# IMU.net
KiCad netlist of a schematic drawn in Altium Designer
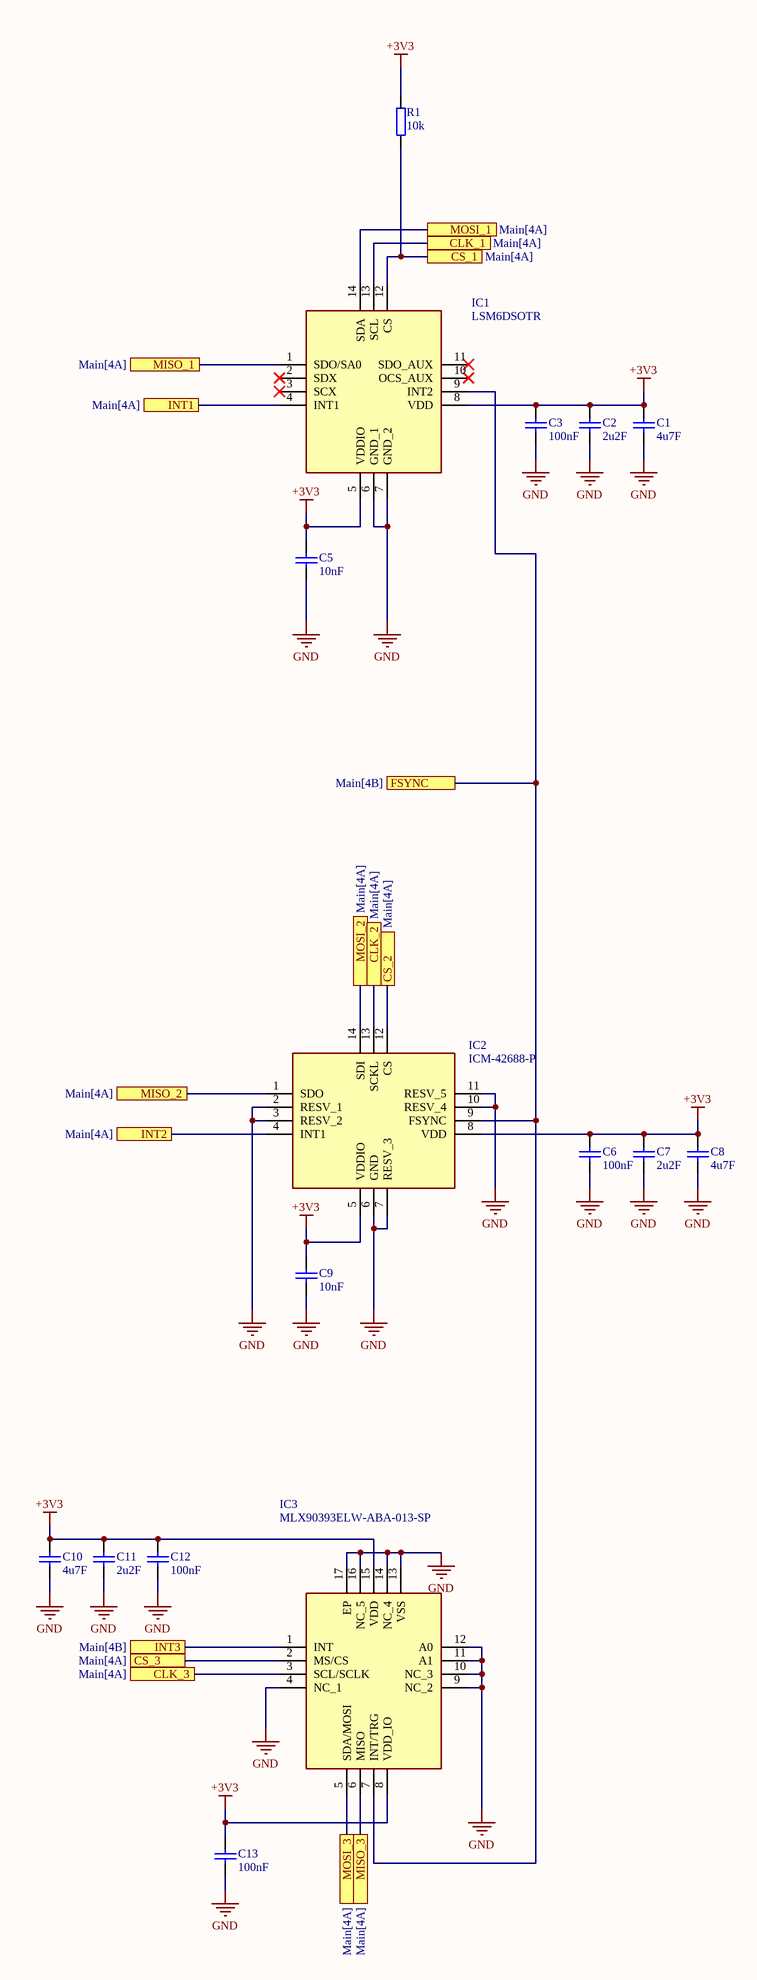
[diagram p0: IMU.SchDoc]

(export (version "E")
  (design (tool "Eeschema 10.0.6"))
  (components
    (comp (ref "C1")
      (value "4u7F")
      (footprint "CAP0805")
      (fields
        (field (name "VOLTAGE") "35V")
        (field (name "MANUFACTURER_PART_NUMBER") "GRM21BR61H475ME51L")
        (field (name "Comment") "Cap0805")
      )
      (libsource (lib "capacitorsSMD") (part "Cap0805"))
    )
    (comp (ref "C2")
      (value "2u2F")
      (footprint "CAP0603")
      (fields
        (field (name "VOLTAGE") "50V")
        (field (name "MANUFACTURER_PART_NUMBER") "GRT188R61H225KE13D")
        (field (name "Comment") "Cap0603")
      )
      (libsource (lib "capacitorsSMD") (part "Cap0603"))
    )
    (comp (ref "C3")
      (value "100nF")
      (footprint "CAP0402")
      (fields
        (field (name "VOLTAGE") "50V")
        (field (name "MANUFACTURER_PART_NUMBER") "GRM155R71H104ME14D")
        (field (name "Comment") "Cap0402")
      )
      (libsource (lib "capacitorsSMD") (part "Cap0402"))
    )
    (comp (ref "C5")
      (value "10nF")
      (footprint "CAP0402")
      (fields
        (field (name "VOLTAGE") "50V")
        (field (name "MANUFACTURER_PART_NUMBER") "GRM155R71H103MA88D")
        (field (name "Comment") "Cap0402")
      )
      (libsource (lib "capacitorsSMD") (part "Cap0402"))
    )
    (comp (ref "C6")
      (value "100nF")
      (footprint "CAP0402")
      (fields
        (field (name "VOLTAGE") "50V")
        (field (name "MANUFACTURER_PART_NUMBER") "GRM155R71H104ME14D")
        (field (name "Comment") "Cap0402")
      )
      (libsource (lib "capacitorsSMD") (part "Cap0402"))
    )
    (comp (ref "C7")
      (value "2u2F")
      (footprint "CAP0603")
      (fields
        (field (name "VOLTAGE") "50V")
        (field (name "MANUFACTURER_PART_NUMBER") "GRT188R61H225KE13D")
        (field (name "Comment") "Cap0603")
      )
      (libsource (lib "capacitorsSMD") (part "Cap0603"))
    )
    (comp (ref "C8")
      (value "4u7F")
      (footprint "CAP0805")
      (fields
        (field (name "VOLTAGE") "35V")
        (field (name "MANUFACTURER_PART_NUMBER") "GRM21BR61H475ME51L")
        (field (name "Comment") "Cap0805")
      )
      (libsource (lib "capacitorsSMD") (part "Cap0805"))
    )
    (comp (ref "C9")
      (value "10nF")
      (footprint "CAP0402")
      (fields
        (field (name "VOLTAGE") "50V")
        (field (name "MANUFACTURER_PART_NUMBER") "GRM155R71H103MA88D")
        (field (name "Comment") "Cap0402")
      )
      (libsource (lib "capacitorsSMD") (part "Cap0402"))
    )
    (comp (ref "C10")
      (value "4u7F")
      (footprint "CAP0805")
      (fields
        (field (name "VOLTAGE") "35V")
        (field (name "MANUFACTURER_PART_NUMBER") "GRM21BR61H475ME51L")
        (field (name "Comment") "Cap0805")
      )
      (libsource (lib "capacitorsSMD") (part "Cap0805"))
    )
    (comp (ref "C11")
      (value "2u2F")
      (footprint "CAP0603")
      (fields
        (field (name "VOLTAGE") "50V")
        (field (name "MANUFACTURER_PART_NUMBER") "GRT188R61H225KE13D")
        (field (name "Comment") "Cap0603")
      )
      (libsource (lib "capacitorsSMD") (part "Cap0603"))
    )
    (comp (ref "C12")
      (value "100nF")
      (footprint "CAP0402")
      (fields
        (field (name "VOLTAGE") "50V")
        (field (name "MANUFACTURER_PART_NUMBER") "GRM155R71H104ME14D")
        (field (name "Comment") "Cap0402")
      )
      (libsource (lib "capacitorsSMD") (part "Cap0402"))
    )
    (comp (ref "C13")
      (value "100nF")
      (footprint "CAP0402")
      (fields
        (field (name "VOLTAGE") "50V")
        (field (name "MANUFACTURER_PART_NUMBER") "GRM155R71H104ME14D")
        (field (name "Comment") "Cap0402")
      )
      (libsource (lib "capacitorsSMD") (part "Cap0402"))
    )
    (comp (ref "IC1")
      (value "LSM6DSOTR")
      (footprint "SamacSys:LSM6DS3USTR")
      (description "Accelerometer")
      (fields (field (name "MOUSER PART NUMBER") "511-LSM6DSOTR"))
      (libsource (lib "*") (part "LSM6DSOTR"))
    )
    (comp (ref "IC2")
      (value "ICM-42688-P")
      (footprint "SamacSys:IIM42352")
      (description "Integrated Circuit")
      (fields (field (name "MOUSER PART NUMBER") "410-ICM-42688-P"))
      (libsource (lib "SamacSys") (part "ICM-42688-P"))
    )
    (comp (ref "IC3")
      (value "MLX90393ELW-ABA-013-SP")
      (footprint "SamacSys:QFN50P300X300X100-17N-D")
      (description "Integrated Circuit")
      (fields (field (name "MOUSER PART NUMBER") "482-90393ELWABA013SP"))
      (libsource (lib "*") (part "MLX90393ELW-ABA-013-SP"))
    )
    (comp (ref "R1")
      (value "10k")
      (footprint "RES0402")
      (fields (field (name "MANUFACTURER_PART_NUMBER") "ERA-2AED103X") (field (name "Comment") "Res0402"))
      (libsource (lib "resistorSMD") (part "Res0402"))
    )
  )
  (nets
    (net (code "1") (name "+3V3") (class "Default")
      (node (ref "C1") (pin "2") (pinfunction "2_2") (pintype "passive"))
      (node (ref "C10") (pin "2") (pinfunction "2_2") (pintype "passive"))
      (node (ref "C11") (pin "2") (pinfunction "2_2") (pintype "passive"))
      (node (ref "C12") (pin "2") (pinfunction "2_2") (pintype "passive"))
      (node (ref "C13") (pin "2") (pinfunction "2_2") (pintype "passive"))
      (node (ref "C2") (pin "2") (pinfunction "2_2") (pintype "passive"))
      (node (ref "C3") (pin "2") (pinfunction "2_2") (pintype "passive"))
      (node (ref "C5") (pin "2") (pinfunction "2_2") (pintype "passive"))
      (node (ref "C6") (pin "2") (pinfunction "2_2") (pintype "passive"))
      (node (ref "C7") (pin "2") (pinfunction "2_2") (pintype "passive"))
      (node (ref "C8") (pin "2") (pinfunction "2_2") (pintype "passive"))
      (node (ref "C9") (pin "2") (pinfunction "2_2") (pintype "passive"))
      (node (ref "IC1") (pin "5") (pinfunction "VDDIO_5") (pintype "passive"))
      (node (ref "IC1") (pin "8") (pinfunction "VDD_8") (pintype "passive"))
      (node (ref "IC2") (pin "5") (pinfunction "VDDIO_5") (pintype "passive"))
      (node (ref "IC2") (pin "8") (pinfunction "VDD_8") (pintype "passive"))
      (node (ref "IC3") (pin "15") (pinfunction "VDD_15") (pintype "passive"))
      (node (ref "IC3") (pin "8") (pinfunction "VDD_IO_8") (pintype "passive"))
      (node (ref "R1") (pin "2") (pinfunction "2_2") (pintype "passive"))
    )
    (net (code "2") (name "/CLK_1") (class "Default")
      (node (ref "IC1") (pin "13") (pinfunction "SCL_13") (pintype "passive"))
    )
    (net (code "3") (name "/CLK_2") (class "Default")
      (node (ref "IC2") (pin "13") (pinfunction "SCKL_13") (pintype "passive"))
    )
    (net (code "4") (name "/CLK_3") (class "Default")
      (node (ref "IC3") (pin "3") (pinfunction "SCL/SCLK_3") (pintype "passive"))
    )
    (net (code "5") (name "/CS_1") (class "Default")
      (node (ref "IC1") (pin "12") (pinfunction "CS_12") (pintype "passive"))
      (node (ref "R1") (pin "1") (pinfunction "1_1") (pintype "passive"))
    )
    (net (code "6") (name "/CS_2") (class "Default")
      (node (ref "IC2") (pin "12") (pinfunction "CS_12") (pintype "passive"))
    )
    (net (code "7") (name "/CS_3") (class "Default")
      (node (ref "IC3") (pin "2") (pinfunction "MS/CS_2") (pintype "passive"))
    )
    (net (code "8") (name "/FSYNC") (class "Default")
      (node (ref "IC1") (pin "9") (pinfunction "INT2_9") (pintype "passive"))
      (node (ref "IC2") (pin "9") (pinfunction "FSYNC_9") (pintype "passive"))
      (node (ref "IC3") (pin "7") (pinfunction "INT/TRG_7") (pintype "passive"))
    )
    (net (code "9") (name "/INT1") (class "Default")
      (node (ref "IC1") (pin "4") (pinfunction "INT1_4") (pintype "passive"))
    )
    (net (code "10") (name "/INT2") (class "Default")
      (node (ref "IC2") (pin "4") (pinfunction "INT1_4") (pintype "passive"))
    )
    (net (code "11") (name "/INT3") (class "Default")
      (node (ref "IC3") (pin "1") (pinfunction "INT_1") (pintype "passive"))
    )
    (net (code "12") (name "/MISO_1") (class "Default")
      (node (ref "IC1") (pin "1") (pinfunction "SDO/SA0_1") (pintype "passive"))
    )
    (net (code "13") (name "/MISO_2") (class "Default")
      (node (ref "IC2") (pin "1") (pinfunction "SDO_1") (pintype "passive"))
    )
    (net (code "14") (name "/MISO_3") (class "Default")
      (node (ref "IC3") (pin "6") (pinfunction "MISO_6") (pintype "passive"))
    )
    (net (code "15") (name "/MOSI_1") (class "Default")
      (node (ref "IC1") (pin "14") (pinfunction "SDA_14") (pintype "passive"))
    )
    (net (code "16") (name "/MOSI_2") (class "Default")
      (node (ref "IC2") (pin "14") (pinfunction "SDI_14") (pintype "passive"))
    )
    (net (code "17") (name "/MOSI_3") (class "Default")
      (node (ref "IC3") (pin "5") (pinfunction "SDA/MOSI_5") (pintype "passive"))
    )
    (net (code "18") (name "GND") (class "Default")
      (node (ref "C1") (pin "1") (pinfunction "1_1") (pintype "passive"))
      (node (ref "C10") (pin "1") (pinfunction "1_1") (pintype "passive"))
      (node (ref "C11") (pin "1") (pinfunction "1_1") (pintype "passive"))
      (node (ref "C12") (pin "1") (pinfunction "1_1") (pintype "passive"))
      (node (ref "C13") (pin "1") (pinfunction "1_1") (pintype "passive"))
      (node (ref "C2") (pin "1") (pinfunction "1_1") (pintype "passive"))
      (node (ref "C3") (pin "1") (pinfunction "1_1") (pintype "passive"))
      (node (ref "C5") (pin "1") (pinfunction "1_1") (pintype "passive"))
      (node (ref "C6") (pin "1") (pinfunction "1_1") (pintype "passive"))
      (node (ref "C7") (pin "1") (pinfunction "1_1") (pintype "passive"))
      (node (ref "C8") (pin "1") (pinfunction "1_1") (pintype "passive"))
      (node (ref "C9") (pin "1") (pinfunction "1_1") (pintype "passive"))
      (node (ref "IC1") (pin "6") (pinfunction "GND_1_6") (pintype "passive"))
      (node (ref "IC1") (pin "7") (pinfunction "GND_2_7") (pintype "passive"))
      (node (ref "IC2") (pin "10") (pinfunction "RESV_4_10") (pintype "passive"))
      (node (ref "IC2") (pin "11") (pinfunction "RESV_5_11") (pintype "passive"))
      (node (ref "IC2") (pin "2") (pinfunction "RESV_1_2") (pintype "passive"))
      (node (ref "IC2") (pin "3") (pinfunction "RESV_2_3") (pintype "passive"))
      (node (ref "IC2") (pin "6") (pinfunction "GND_6") (pintype "passive"))
      (node (ref "IC2") (pin "7") (pinfunction "RESV_3_7") (pintype "passive"))
      (node (ref "IC3") (pin "10") (pinfunction "NC_3_10") (pintype "passive"))
      (node (ref "IC3") (pin "11") (pinfunction "A1_11") (pintype "passive"))
      (node (ref "IC3") (pin "12") (pinfunction "A0_12") (pintype "passive"))
      (node (ref "IC3") (pin "13") (pinfunction "VSS_13") (pintype "passive"))
      (node (ref "IC3") (pin "14") (pinfunction "NC_4_14") (pintype "passive"))
      (node (ref "IC3") (pin "16") (pinfunction "NC_5_16") (pintype "passive"))
      (node (ref "IC3") (pin "17") (pinfunction "EP_17") (pintype "passive"))
      (node (ref "IC3") (pin "4") (pinfunction "NC_1_4") (pintype "passive"))
      (node (ref "IC3") (pin "9") (pinfunction "NC_2_9") (pintype "passive"))
    )
    (net (code "19") (name "unconnected-(IC1-OCS_AUX-Pad10)") (class "Default")
      (node (ref "IC1") (pin "10") (pinfunction "OCS_AUX_10") (pintype "passive+no_connect"))
    )
    (net (code "20") (name "unconnected-(IC1-SCX-Pad3)") (class "Default")
      (node (ref "IC1") (pin "3") (pinfunction "SCX_3") (pintype "passive+no_connect"))
    )
    (net (code "21") (name "unconnected-(IC1-SDO_AUX-Pad11)") (class "Default")
      (node (ref "IC1") (pin "11") (pinfunction "SDO_AUX_11") (pintype "passive+no_connect"))
    )
    (net (code "22") (name "unconnected-(IC1-SDX-Pad2)") (class "Default")
      (node (ref "IC1") (pin "2") (pinfunction "SDX_2") (pintype "passive+no_connect"))
    )
  )
)
